# Power-Sheet-2.net
KiCad netlist of a schematic drawn in Altium Designer
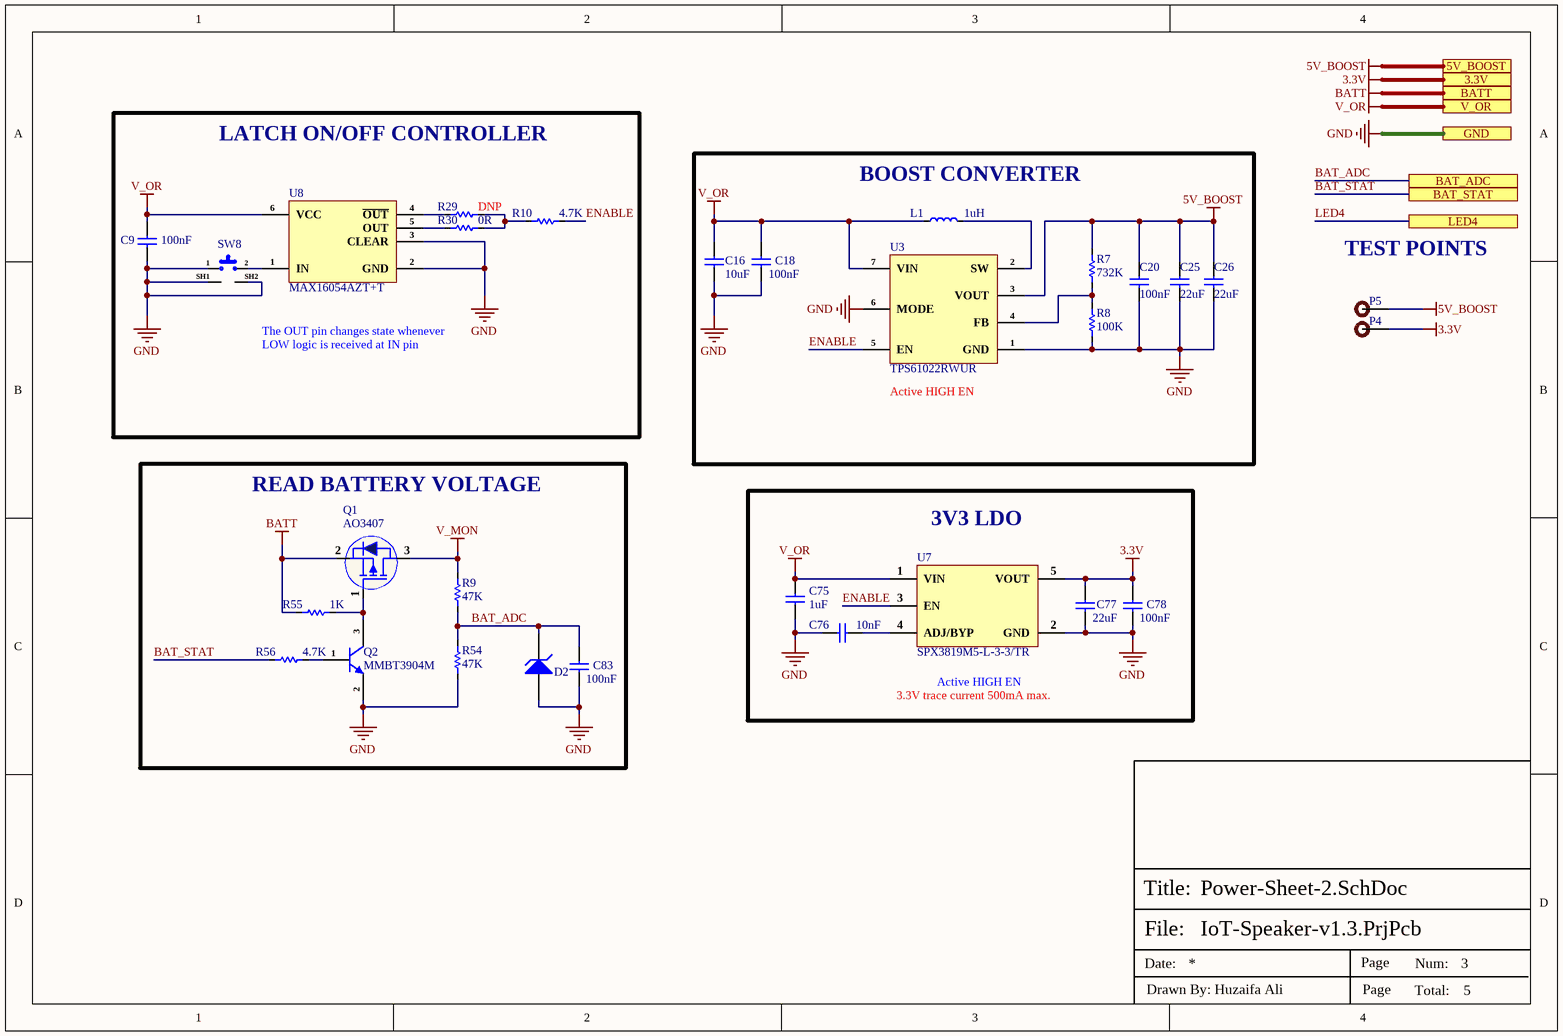
[diagram p0: Power-Sheet-2.SchDoc]

(export (version "E")
  (design (tool "Eeschema 10.0.6"))
  (components
    (comp (ref "C9")
      (value "100nF")
      (footprint "Cap-0402")
      (description "CAP CER 0.1UF 25V X5R 0402")
      (fields
        (field (name "MANUFACTURER") "Yageo")
        (field (name "MANUFACTURER PART NUMBER") "CC0402KRX5R8BB104")
      )
      (libsource (lib "eSpark_centralized_Library(2022)") (part "CC0402KRX5R8BB104"))
    )
    (comp (ref "C16")
      (value "10uF")
      (footprint "Cap-0805")
      (description "CAP CER 10UF 25V X5R 0805")
      (fields
        (field (name "MANUFACTURER") "Yageo")
        (field (name "MANUFACTURER PART NUMBER") "CC0805KKX5R8BB106")
      )
      (libsource (lib "eSpark_centralized_Library(2022)") (part "CC0805KKX5R8BB106"))
    )
    (comp (ref "C18")
      (value "100nF")
      (footprint "Cap-0402")
      (description "CAP CER 0.1UF 25V X5R 0402")
      (fields
        (field (name "MANUFACTURER") "Yageo")
        (field (name "MANUFACTURER PART NUMBER") "CC0402KRX5R8BB104")
      )
      (libsource (lib "eSpark_centralized_Library(2022)") (part "CC0402KRX5R8BB104"))
    )
    (comp (ref "C20")
      (value "100nF")
      (footprint "Cap-0402")
      (description "CAP CER 0.1UF 25V X5R 0402")
      (fields
        (field (name "MANUFACTURER") "Yageo")
        (field (name "MANUFACTURER PART NUMBER") "CC0402KRX5R8BB104")
      )
      (libsource (lib "eSpark_centralized_Library(2022)") (part "CC0402KRX5R8BB104"))
    )
    (comp (ref "C25")
      (value "22uF")
      (footprint "Cap-0603")
      (description "CAP CER 22UF 10V X5R 0603")
      (fields
        (field (name "MANUFACTURER") "Yageo")
        (field (name "MANUFACTURER PART NUMBER") "CC0603MRX5R6BB226")
      )
      (libsource (lib "eSpark_centralized_Library(2022)") (part "CC0603MRX5R6BB226"))
    )
    (comp (ref "C26")
      (value "22uF")
      (footprint "Cap-0603")
      (description "CAP CER 22UF 10V X5R 0603")
      (fields
        (field (name "MANUFACTURER") "Yageo")
        (field (name "MANUFACTURER PART NUMBER") "CC0603MRX5R6BB226")
      )
      (libsource (lib "eSpark_centralized_Library(2022)") (part "CC0603MRX5R6BB226"))
    )
    (comp (ref "C75")
      (value "1uF")
      (footprint "Cap-0603")
      (description "CAP CER 1UF 25V X5R 0603")
      (fields
        (field (name "MANUFACTURER") "Yageo")
        (field (name "MANUFACTURER PART NUMBER") "CC0603KRX5R8BB105")
      )
      (libsource (lib "eSpark_centralized_Library(2022)") (part "CC0603KRX5R8BB105"))
    )
    (comp (ref "C76")
      (value "10nF")
      (footprint "Cap-0603")
      (description "CAP CER 10000PF 50V C0G/NPO 0603")
      (fields
        (field (name "MANUFACTURER") "Yageo")
        (field (name "MANUFACTURER PART NUMBER") "CC0603JRNPO9BN103")
      )
      (libsource (lib "eSpark_centralized_Library(2022)") (part "CC0603JRNPO9BN103"))
    )
    (comp (ref "C77")
      (value "22uF")
      (footprint "Cap-0603")
      (description "CAP CER 22UF 10V X5R 0603")
      (fields
        (field (name "MANUFACTURER") "Yageo")
        (field (name "MANUFACTURER PART NUMBER") "CC0603MRX5R6BB226")
      )
      (libsource (lib "eSpark_centralized_Library(2022)") (part "CC0603MRX5R6BB226"))
    )
    (comp (ref "C78")
      (value "100nF")
      (footprint "Cap-0402")
      (description "CAP CER 0.1UF 25V X5R 0402")
      (fields
        (field (name "MANUFACTURER") "Yageo")
        (field (name "MANUFACTURER PART NUMBER") "CC0402KRX5R8BB104")
      )
      (libsource (lib "eSpark_centralized_Library(2022)") (part "CC0402KRX5R8BB104"))
    )
    (comp (ref "C83")
      (value "100nF")
      (footprint "Cap-0402")
      (description "CAP CER 0.1UF 25V X5R 0402")
      (fields
        (field (name "MANUFACTURER") "Yageo")
        (field (name "MANUFACTURER PART NUMBER") "CC0402KRX5R8BB104")
      )
      (libsource (lib "eSpark_centralized_Library(2022)") (part "CC0402KRX5R8BB104"))
    )
    (comp (ref "D2")
      (value "MM3Z3V3B")
      (footprint "SOD323F")
      (description "DIODE ZENER 3.3V 200MW SOD323F")
      (fields (field (name "MANUFACTURER") "ON Semiconductor / Fairchild") (field (name "TOLERANCE") "2%"))
      (libsource (lib "eSpark_centralized_Library(2022)") (part "MM3Z3V3B"))
    )
    (comp (ref "L1")
      (value "1uH")
      (footprint "MPIT6045-1R0N-LF")
      (description "5.15A 1uH ±30% SMD Power Inductors ROHS")
      (fields
        (field (name "MANUFACTURER") "microgate")
        (field (name "MANUFACTURER PART NUMBER") "MPIT6045-1R0N-LF")
      )
      (libsource (lib "eSpark_centralized_Library(2022)") (part "MPIT6045-1R0N-LF"))
    )
    (comp (ref "P4")
      (value "TEST POINT")
      (footprint "Test-point")
      (description "Test Point ON")
      (libsource (lib "eSpark_centralized_Library(2022)") (part "TEST POINT"))
    )
    (comp (ref "P5")
      (value "TEST POINT")
      (footprint "Test-point")
      (description "Test Point ON")
      (libsource (lib "eSpark_centralized_Library(2022)") (part "TEST POINT"))
    )
    (comp (ref "Q1")
      (value "AO3407")
      (footprint "SOT-23")
      (description "30V 4.1A 60mΩ@10V,4.1A 350mW 3V@250uA P Channel SOT-23 MOSFETs ROHS")
      (fields (field (name "MANUFACTURER") "Guangdong Hottech") (field (name "LCSC PART NUMBER") "C181093"))
      (libsource (lib "eSpark_centralized_Library(2022)") (part "AO3407"))
    )
    (comp (ref "Q2")
      (value "MMBT3904M")
      (footprint "SOT-723")
      (fields (field (name "MANUFACTURER") "TECH PUBLIC") (field (name "LCSC PART NUMBER") "C2923360"))
      (libsource (lib "eSpark_centralized_Library(2022)") (part "MMBT3904M"))
    )
    (comp (ref "R7")
      (value "732K")
      (footprint "Res-0402")
      (description "±1% 732kΩ 0402 Chip Resistor - Surface Mount ROHS")
      (fields
        (field (name "MANUFACTURER") "FOJAN")
        (field (name "MANUFACTURER PART NUMBER") "FRC0402F7323TS")
      )
      (libsource (lib "eSpark_centralized_Library(2022)") (part "FRC0402F7323TS"))
    )
    (comp (ref "R8")
      (value "100K")
      (footprint "Res-0603")
      (description "RES SMD 100K OHM 0.1% 1/10W 0603")
      (fields
        (field (name "MANUFACTURER") "Yageo")
        (field (name "MANUFACTURER PART NUMBER") "RT0603BRD07100KL")
      )
      (libsource (lib "eSpark_centralized_Library(2022)") (part "RT0603BRD07100KL"))
    )
    (comp (ref "R9")
      (value "47K")
      (footprint "Res-0603")
      (description "RES 47K OHM 5% 1/10W 0603")
      (fields
        (field (name "MANUFACTURER") "Yageo")
        (field (name "MANUFACTURER PART NUMBER") "RC0603JR-0747KL")
      )
      (libsource (lib "eSpark_centralized_Library(2022)") (part "RC0603JR-0747KL"))
    )
    (comp (ref "R10")
      (value "4.7K")
      (footprint "Res-0603")
      (description "RES SMD 4.7K OHM 5% 1/10W 0603")
      (fields
        (field (name "MANUFACTURER") "Yageo")
        (field (name "MANUFACTURER PART NUMBER") "RC0603JR-074K7L")
      )
      (libsource (lib "eSpark Libraries") (part "RC0603JR-074K7L"))
    )
    (comp (ref "R29")
      (value "DNP")
      (footprint "Res-0603")
      (description "RES SMD 0R, 1%, 0.1W, 0603")
      (fields
        (field (name "MANUFACTURER") "Yageo")
        (field (name "MANUFACTURER PART NUMBER") "RC0603FR-070RL")
      )
      (libsource (lib "eSpark Libraries") (part "RC0603FR-070RL"))
    )
    (comp (ref "R30")
      (value "0R")
      (footprint "Res-0603")
      (description "RES SMD 0R, 1%, 0.1W, 0603")
      (fields
        (field (name "MANUFACTURER") "Yageo")
        (field (name "MANUFACTURER PART NUMBER") "RC0603FR-070RL")
      )
      (libsource (lib "eSpark Libraries") (part "RC0603FR-070RL"))
    )
    (comp (ref "R54")
      (value "47K")
      (footprint "Res-0603")
      (description "RES 47K OHM 5% 1/10W 0603")
      (fields
        (field (name "MANUFACTURER") "Yageo")
        (field (name "MANUFACTURER PART NUMBER") "RC0603JR-0747KL")
      )
      (libsource (lib "eSpark_centralized_Library(2022)") (part "RC0603JR-0747KL"))
    )
    (comp (ref "R55")
      (value "1K")
      (footprint "Res-0603")
      (description "RES SMD 1K OHM 1% 1/10W 0603")
      (fields
        (field (name "MANUFACTURER") "Yageo")
        (field (name "MANUFACTURER PART NUMBER") "RC0603FR-071KL")
      )
      (libsource (lib "eSpark_centralized_Library(2022)") (part "RC0603FR-071KL"))
    )
    (comp (ref "R56")
      (value "4.7K")
      (footprint "Res-0603")
      (description "RES SMD 4.7K OHM 5% 1/10W 0603")
      (fields
        (field (name "MANUFACTURER") "Yageo")
        (field (name "MANUFACTURER PART NUMBER") "RC0603JR-074K7L")
      )
      (libsource (lib "eSpark_centralized_Library(2022)") (part "RC0603JR-074K7L"))
    )
    (comp (ref "SW8")
      (value "TS-1087E-B3D2")
      (footprint "TS-1087E-B3D2")
      (description "Plugin-4P,7.7x3.5mm Tactile Switches ROHS")
      (fields (field (name "MANUFACTURER") "Yuandi") (field (name "LCSC PART NUMBER") "C541963"))
      (libsource (lib "eSpark Libraries") (part "TS-1087E-B3D2"))
    )
    (comp (ref "U3")
      (value "TPS61022RWUR")
      (footprint "7-VQFN-HR (2x2)")
      (description "8-A boost converter with 0.5-V ultra-low input voltage 7-VQFN-HR -40 to 125")
      (fields (field (name "MANUFACTURER") "Texas Instruments") (field (name "LCSC PART NUMBER") "C915088"))
      (libsource (lib "Centralize") (part "TPS61022RWUR"))
    )
    (comp (ref "U7")
      (value "SPX3819M5-L-3-3/TR")
      (footprint "SOT-23-5")
      (description "SPX3819 Series 3.3 V 500 mA Fixed Output SMT LDO Regulator - SOT-23-5")
      (fields (field (name "MANUFACTURER") "MaxLinear") (field (name "LCSC PART NUMBER") "C9055"))
      (libsource (lib "eSpark_centralized_Library(2022)") (part "SPX3819M5-L-3-3/TR"))
    )
    (comp (ref "U8")
      (value "MAX16054AZT+T")
      (footprint "TSOT-23-6")
      (description "IC CNTRLR ON/OFF W/DEB TSOT23-6")
      (fields (field (name "MANUFACTURER") "Maxim") (field (name "LCSC PART NUMBER") "C79401"))
      (libsource (lib "eSpark_centralized_Library(2022)") (part "MAX16054AZT+T"))
    )
  )
  (nets
    (net (code "1") (name "/BAT_ADC") (class "Default")
      (node (ref "C83") (pin "2") (pinfunction "2_2") (pintype "passive"))
      (node (ref "D2") (pin "2") (pinfunction "K_2") (pintype "passive"))
      (node (ref "R54") (pin "2") (pinfunction "2_2") (pintype "passive"))
      (node (ref "R9") (pin "1") (pinfunction "1_1") (pintype "passive"))
    )
    (net (code "2") (name "/BAT_STAT") (class "Default")
      (node (ref "R56") (pin "1") (pinfunction "1_1") (pintype "passive"))
    )
    (net (code "3") (name "/ENABLE") (class "Default")
      (node (ref "R10") (pin "2") (pinfunction "2_2") (pintype "passive"))
      (node (ref "U3") (pin "5") (pinfunction "EN_5") (pintype "passive"))
      (node (ref "U7") (pin "3") (pinfunction "EN_3") (pintype "passive"))
    )
    (net (code "5") (name "3.3V") (class "Default")
      (node (ref "C77") (pin "2") (pinfunction "2_2") (pintype "passive"))
      (node (ref "C78") (pin "2") (pinfunction "2_2") (pintype "passive"))
      (node (ref "P4") (pin "1") (pinfunction "1_1") (pintype "passive"))
      (node (ref "U7") (pin "5") (pinfunction "VOUT_5") (pintype "passive"))
    )
    (net (code "6") (name "5V_BOOST") (class "Default")
      (node (ref "C20") (pin "2") (pinfunction "2_2") (pintype "passive"))
      (node (ref "C25") (pin "2") (pinfunction "2_2") (pintype "passive"))
      (node (ref "C26") (pin "2") (pinfunction "2_2") (pintype "passive"))
      (node (ref "P5") (pin "1") (pinfunction "1_1") (pintype "passive"))
      (node (ref "R7") (pin "2") (pinfunction "2_2") (pintype "passive"))
      (node (ref "U3") (pin "3") (pinfunction "VOUT_3") (pintype "passive"))
    )
    (net (code "7") (name "BATT") (class "Default")
      (node (ref "Q1") (pin "2") (pinfunction "S_2") (pintype "passive"))
      (node (ref "R55") (pin "1") (pinfunction "1_1") (pintype "passive"))
    )
    (net (code "8") (name "GND") (class "Default")
      (node (ref "C16") (pin "1") (pinfunction "1_1") (pintype "passive"))
      (node (ref "C18") (pin "1") (pinfunction "1_1") (pintype "passive"))
      (node (ref "C20") (pin "1") (pinfunction "1_1") (pintype "passive"))
      (node (ref "C25") (pin "1") (pinfunction "1_1") (pintype "passive"))
      (node (ref "C26") (pin "1") (pinfunction "1_1") (pintype "passive"))
      (node (ref "C75") (pin "1") (pinfunction "1_1") (pintype "passive"))
      (node (ref "C76") (pin "1") (pinfunction "1_1") (pintype "passive"))
      (node (ref "C77") (pin "1") (pinfunction "1_1") (pintype "passive"))
      (node (ref "C78") (pin "1") (pinfunction "1_1") (pintype "passive"))
      (node (ref "C83") (pin "1") (pinfunction "1_1") (pintype "passive"))
      (node (ref "C9") (pin "1") (pinfunction "1_1") (pintype "passive"))
      (node (ref "D2") (pin "1") (pinfunction "A_1") (pintype "passive"))
      (node (ref "Q2") (pin "2") (pinfunction "E_2") (pintype "passive"))
      (node (ref "R54") (pin "1") (pinfunction "1_1") (pintype "passive"))
      (node (ref "R8") (pin "1") (pinfunction "1_1") (pintype "passive"))
      (node (ref "SW8") (pin "1") (pinfunction "1_1") (pintype "passive"))
      (node (ref "SW8") (pin "SH1") (pinfunction "SH1_SH1") (pintype "passive"))
      (node (ref "SW8") (pin "SH2") (pinfunction "SH2_SH2") (pintype "passive"))
      (node (ref "U3") (pin "1") (pinfunction "GND_1") (pintype "passive"))
      (node (ref "U3") (pin "6") (pinfunction "MODE_6") (pintype "passive"))
      (node (ref "U7") (pin "2") (pinfunction "GND_2") (pintype "passive"))
      (node (ref "U8") (pin "2") (pinfunction "GND_2") (pintype "passive"))
      (node (ref "U8") (pin "3") (pinfunction "CLEAR_3") (pintype "passive"))
    )
    (net (code "9") (name "Net-(Q1-G)") (class "Default")
      (node (ref "Q1") (pin "1") (pinfunction "G_1") (pintype "passive"))
      (node (ref "Q2") (pin "3") (pinfunction "C_3") (pintype "passive"))
      (node (ref "R55") (pin "2") (pinfunction "2_2") (pintype "passive"))
    )
    (net (code "10") (name "Net-(Q2-B)") (class "Default")
      (node (ref "Q2") (pin "1") (pinfunction "B_1") (pintype "passive"))
      (node (ref "R56") (pin "2") (pinfunction "2_2") (pintype "passive"))
    )
    (net (code "11") (name "Net-(R10-Pad1)") (class "Default")
      (node (ref "R10") (pin "1") (pinfunction "1_1") (pintype "passive"))
      (node (ref "R29") (pin "2") (pinfunction "2_2") (pintype "passive"))
      (node (ref "R30") (pin "2") (pinfunction "2_2") (pintype "passive"))
    )
    (net (code "12") (name "Net-(U3-FB)") (class "Default")
      (node (ref "R7") (pin "1") (pinfunction "1_1") (pintype "passive"))
      (node (ref "R8") (pin "2") (pinfunction "2_2") (pintype "passive"))
      (node (ref "U3") (pin "4") (pinfunction "FB_4") (pintype "passive"))
    )
    (net (code "13") (name "Net-(U3-SW)") (class "Default")
      (node (ref "L1") (pin "2") (pinfunction "2_2") (pintype "passive"))
      (node (ref "U3") (pin "2") (pinfunction "SW_2") (pintype "passive"))
    )
    (net (code "14") (name "Net-(U7-ADJ{slash}BYP)") (class "Default")
      (node (ref "C76") (pin "2") (pinfunction "2_2") (pintype "passive"))
      (node (ref "U7") (pin "4") (pinfunction "ADJ/BYP_4") (pintype "passive"))
    )
    (net (code "15") (name "Net-(U8-IN)") (class "Default")
      (node (ref "SW8") (pin "2") (pinfunction "2_2") (pintype "passive"))
      (node (ref "U8") (pin "1") (pinfunction "IN_1") (pintype "passive"))
    )
    (net (code "16") (name "Net-(U8-OUT)") (class "Default")
      (node (ref "R30") (pin "1") (pinfunction "1_1") (pintype "passive"))
      (node (ref "U8") (pin "5") (pinfunction "OUT_5") (pintype "passive"))
    )
    (net (code "17") (name "Net-(U8-~{OUT})") (class "Default")
      (node (ref "R29") (pin "1") (pinfunction "1_1") (pintype "passive"))
      (node (ref "U8") (pin "4") (pinfunction "~{OUT}_4") (pintype "passive"))
    )
    (net (code "18") (name "V_MON") (class "Default")
      (node (ref "Q1") (pin "3") (pinfunction "D_3") (pintype "passive"))
      (node (ref "R9") (pin "2") (pinfunction "2_2") (pintype "passive"))
    )
    (net (code "19") (name "V_OR") (class "Default")
      (node (ref "C16") (pin "2") (pinfunction "2_2") (pintype "passive"))
      (node (ref "C18") (pin "2") (pinfunction "2_2") (pintype "passive"))
      (node (ref "C75") (pin "2") (pinfunction "2_2") (pintype "passive"))
      (node (ref "C9") (pin "2") (pinfunction "2_2") (pintype "passive"))
      (node (ref "L1") (pin "1") (pinfunction "1_1") (pintype "passive"))
      (node (ref "U3") (pin "7") (pinfunction "VIN_7") (pintype "passive"))
      (node (ref "U7") (pin "1") (pinfunction "VIN_1") (pintype "passive"))
      (node (ref "U8") (pin "6") (pinfunction "VCC_6") (pintype "passive"))
    )
  )
)
